# Stm32.net
KiCad netlist of a schematic drawn in Altium Designer
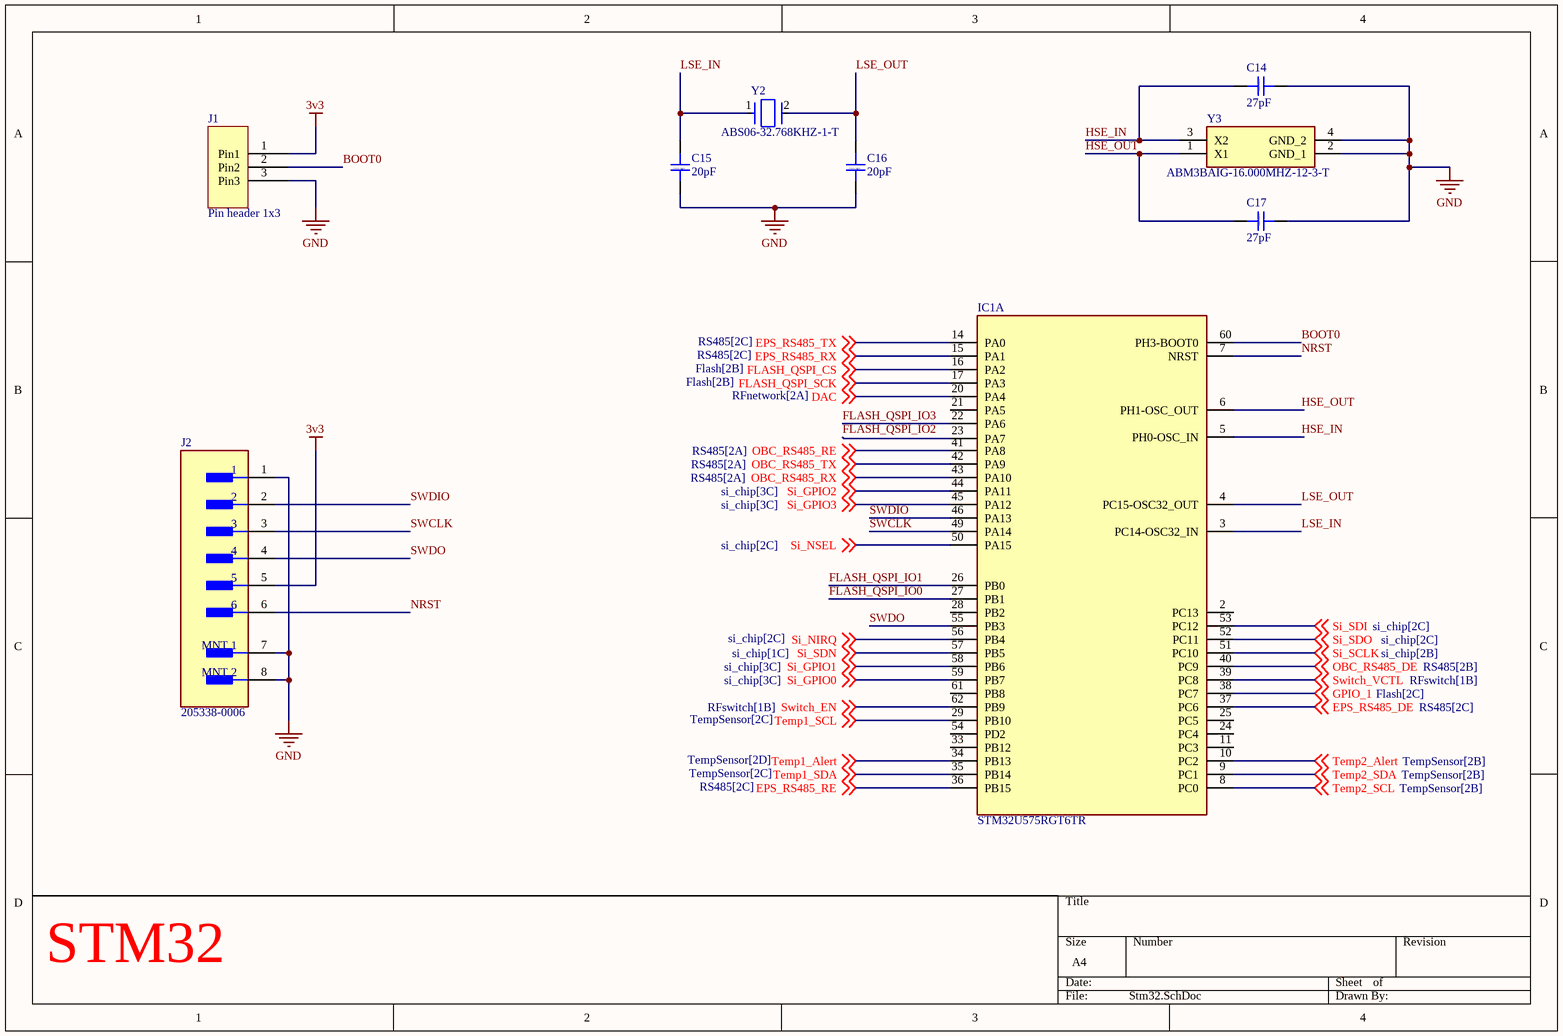
[diagram p0:  Stm32.SchDoc]

(export (version "E")
  (design (tool "Eeschema 10.0.6"))
  (components
    (comp (ref "C14")
      (value "27pF")
      (footprint "CAP_0603")
      (description "Capacitor SMD 0603 RATED")
      (libsource (lib "STeRG-Passives-Standard") (part "Capacitor-SMD-0603"))
    )
    (comp (ref "C15")
      (value "20pF")
      (footprint "CAP_0603")
      (description "Capacitor SMD 0603 RATED")
      (libsource (lib "STeRG-Passives-Standard") (part "Capacitor-SMD-0603"))
    )
    (comp (ref "C16")
      (value "20pF")
      (footprint "CAP_0603")
      (description "Capacitor SMD 0603 RATED")
      (libsource (lib "STeRG-Passives-Standard") (part "Capacitor-SMD-0603"))
    )
    (comp (ref "C17")
      (value "27pF")
      (footprint "CAP_0603")
      (description "Capacitor SMD 0603 RATED")
      (libsource (lib "STeRG-Passives-Standard") (part "Capacitor-SMD-0603"))
    )
    (comp (ref "IC1")
      (value "STM32U575RGT6TR")
      (footprint "QFP50P1200X1200X160-64N")
      (description "Integrated Circuit")
      (fields (field (name "MOUSER PART NUMBER") "511-STM32U575RGT6TR"))
      (libsource (lib "STeRG-ICs-Standard") (part "STM32U575RGT6TR"))
    )
    (comp (ref "J1")
      (value "Pin header 1x3")
      (footprint "HEADER 3")
      (libsource (lib "SamacSys") (part "Pin header 1x3"))
    )
    (comp (ref "J2")
      (value "205338-0006")
      (footprint "FP-2053380006-MFG")
      (libsource (lib "Altium Content Vault") (part "ed24c53d9ba001d1a2a686240a95171"))
    )
    (comp (ref "Y2")
      (value "ABS06-32.768KHZ-1-T")
      (footprint "FP-ABS06-MFG")
      (description "CRYSTAL 32.7680KHZ 12.5PF SMD")
      (fields (field (name "TOLERANCE") "10ppm"))
      (libsource (lib "Altium Content Vault") (part "c23a69dc6c9e2f18f2079038eb95dd1"))
    )
    (comp (ref "Y3")
      (value "ABM3BAIG-16.000MHZ-12-3-T")
      (footprint "SamacSys:ABM3BAIG")
      (description "Crystal or Oscillator")
      (libsource (lib "SamacSys") (part "ABM3BAIG-16.000MHZ-12-3-T"))
    )
  )
  (nets
    (net (code "1") (name "/BOOT0") (class "Default")
      (node (ref "IC1") (pin "60") (pinfunction "PH3-BOOT0_60") (pintype "passive"))
      (node (ref "J1") (pin "2") (pinfunction "Pin2_2") (pintype "passive"))
    )
    (net (code "2") (name "/FLASH_QSPI_IO0") (class "Default")
      (node (ref "IC1") (pin "27") (pinfunction "PB1_27") (pintype "passive"))
    )
    (net (code "3") (name "/FLASH_QSPI_IO1") (class "Default")
      (node (ref "IC1") (pin "26") (pinfunction "PB0_26") (pintype "passive"))
    )
    (net (code "4") (name "/FLASH_QSPI_IO2") (class "Default")
      (node (ref "IC1") (pin "23") (pinfunction "PA7_23") (pintype "passive"))
    )
    (net (code "5") (name "/FLASH_QSPI_IO3") (class "Default")
      (node (ref "IC1") (pin "22") (pinfunction "PA6_22") (pintype "passive"))
    )
    (net (code "6") (name "/HSE_IN") (class "Default")
      (node (ref "C14") (pin "1") (pinfunction "1_1") (pintype "passive"))
      (node (ref "IC1") (pin "5") (pinfunction "PH0-OSC_IN_5") (pintype "passive"))
      (node (ref "Y3") (pin "3") (pinfunction "X2_3") (pintype "passive"))
    )
    (net (code "7") (name "/HSE_OUT") (class "Default")
      (node (ref "C17") (pin "1") (pinfunction "1_1") (pintype "passive"))
      (node (ref "IC1") (pin "6") (pinfunction "PH1-OSC_OUT_6") (pintype "passive"))
      (node (ref "Y3") (pin "1") (pinfunction "X1_1") (pintype "passive"))
    )
    (net (code "8") (name "/LSE_IN") (class "Default")
      (node (ref "C15") (pin "2") (pinfunction "2_2") (pintype "passive"))
      (node (ref "IC1") (pin "3") (pinfunction "PC14-OSC32_IN_3") (pintype "passive"))
      (node (ref "Y2") (pin "1") (pinfunction "1_1") (pintype "passive"))
    )
    (net (code "9") (name "/LSE_OUT") (class "Default")
      (node (ref "C16") (pin "2") (pinfunction "2_2") (pintype "passive"))
      (node (ref "IC1") (pin "4") (pinfunction "PC15-OSC32_OUT_4") (pintype "passive"))
      (node (ref "Y2") (pin "2") (pinfunction "2_2") (pintype "passive"))
    )
    (net (code "10") (name "/NRST") (class "Default")
      (node (ref "IC1") (pin "7") (pinfunction "NRST_7") (pintype "passive"))
      (node (ref "J2") (pin "6") (pinfunction "6_6") (pintype "passive"))
    )
    (net (code "11") (name "/SWCLK") (class "Default")
      (node (ref "IC1") (pin "49") (pinfunction "PA14_49") (pintype "passive"))
      (node (ref "J2") (pin "3") (pinfunction "3_3") (pintype "passive"))
    )
    (net (code "12") (name "/SWDIO") (class "Default")
      (node (ref "IC1") (pin "46") (pinfunction "PA13_46") (pintype "passive"))
      (node (ref "J2") (pin "2") (pinfunction "2_2") (pintype "passive"))
    )
    (net (code "13") (name "/SWDO") (class "Default")
      (node (ref "IC1") (pin "55") (pinfunction "PB3_55") (pintype "passive"))
      (node (ref "J2") (pin "4") (pinfunction "4_4") (pintype "passive"))
    )
    (net (code "14") (name "3v3") (class "Default")
      (node (ref "J1") (pin "1") (pinfunction "Pin1_1") (pintype "passive"))
      (node (ref "J2") (pin "5") (pinfunction "5_5") (pintype "passive"))
    )
    (net (code "15") (name "DAC") (class "Default")
      (node (ref "IC1") (pin "20") (pinfunction "PA4_20") (pintype "passive"))
    )
    (net (code "16") (name "EPS_RS485_DE") (class "Default")
      (node (ref "IC1") (pin "37") (pinfunction "PC6_37") (pintype "passive"))
    )
    (net (code "17") (name "EPS_RS485_RE") (class "Default")
      (node (ref "IC1") (pin "36") (pinfunction "PB15_36") (pintype "passive"))
    )
    (net (code "18") (name "EPS_RS485_RX") (class "Default")
      (node (ref "IC1") (pin "15") (pinfunction "PA1_15") (pintype "passive"))
    )
    (net (code "19") (name "EPS_RS485_TX") (class "Default")
      (node (ref "IC1") (pin "14") (pinfunction "PA0_14") (pintype "passive"))
    )
    (net (code "20") (name "FLASH_QSPI_CS") (class "Default")
      (node (ref "IC1") (pin "16") (pinfunction "PA2_16") (pintype "passive"))
    )
    (net (code "21") (name "FLASH_QSPI_SCK") (class "Default")
      (node (ref "IC1") (pin "17") (pinfunction "PA3_17") (pintype "passive"))
    )
    (net (code "22") (name "GND") (class "Default")
      (node (ref "C14") (pin "2") (pinfunction "2_2") (pintype "passive"))
      (node (ref "C15") (pin "1") (pinfunction "1_1") (pintype "passive"))
      (node (ref "C16") (pin "1") (pinfunction "1_1") (pintype "passive"))
      (node (ref "C17") (pin "2") (pinfunction "2_2") (pintype "passive"))
      (node (ref "J1") (pin "3") (pinfunction "Pin3_3") (pintype "passive"))
      (node (ref "J2") (pin "1") (pinfunction "1_1") (pintype "passive"))
      (node (ref "J2") (pin "7") (pinfunction "MNT_1_7") (pintype "passive"))
      (node (ref "J2") (pin "8") (pinfunction "MNT_2_8") (pintype "passive"))
      (node (ref "Y3") (pin "2") (pinfunction "GND_1_2") (pintype "passive"))
      (node (ref "Y3") (pin "4") (pinfunction "GND_2_4") (pintype "passive"))
    )
    (net (code "23") (name "GPIO_1") (class "Default")
      (node (ref "IC1") (pin "38") (pinfunction "PC7_38") (pintype "passive"))
    )
    (net (code "24") (name "OBC_RS485_DE") (class "Default")
      (node (ref "IC1") (pin "40") (pinfunction "PC9_40") (pintype "passive"))
    )
    (net (code "25") (name "OBC_RS485_RE") (class "Default")
      (node (ref "IC1") (pin "41") (pinfunction "PA8_41") (pintype "passive"))
    )
    (net (code "26") (name "OBC_RS485_RX") (class "Default")
      (node (ref "IC1") (pin "43") (pinfunction "PA10_43") (pintype "passive"))
    )
    (net (code "27") (name "OBC_RS485_TX") (class "Default")
      (node (ref "IC1") (pin "42") (pinfunction "PA9_42") (pintype "passive"))
    )
    (net (code "28") (name "Si_GPIO0") (class "Default")
      (node (ref "IC1") (pin "59") (pinfunction "PB7_59") (pintype "passive"))
    )
    (net (code "29") (name "Si_GPIO1") (class "Default")
      (node (ref "IC1") (pin "58") (pinfunction "PB6_58") (pintype "passive"))
    )
    (net (code "30") (name "Si_GPIO2") (class "Default")
      (node (ref "IC1") (pin "44") (pinfunction "PA11_44") (pintype "passive"))
    )
    (net (code "31") (name "Si_GPIO3") (class "Default")
      (node (ref "IC1") (pin "45") (pinfunction "PA12_45") (pintype "passive"))
    )
    (net (code "32") (name "Si_NIRQ") (class "Default")
      (node (ref "IC1") (pin "56") (pinfunction "PB4_56") (pintype "passive"))
    )
    (net (code "33") (name "Si_NSEL") (class "Default")
      (node (ref "IC1") (pin "50") (pinfunction "PA15_50") (pintype "passive"))
    )
    (net (code "34") (name "Si_SCLK") (class "Default")
      (node (ref "IC1") (pin "51") (pinfunction "PC10_51") (pintype "passive"))
    )
    (net (code "35") (name "Si_SDI") (class "Default")
      (node (ref "IC1") (pin "53") (pinfunction "PC12_53") (pintype "passive"))
    )
    (net (code "36") (name "Si_SDN") (class "Default")
      (node (ref "IC1") (pin "57") (pinfunction "PB5_57") (pintype "passive"))
    )
    (net (code "37") (name "Si_SDO") (class "Default")
      (node (ref "IC1") (pin "52") (pinfunction "PC11_52") (pintype "passive"))
    )
    (net (code "38") (name "Switch_EN") (class "Default")
      (node (ref "IC1") (pin "62") (pinfunction "PB9_62") (pintype "passive"))
    )
    (net (code "39") (name "Switch_VCTL") (class "Default")
      (node (ref "IC1") (pin "39") (pinfunction "PC8_39") (pintype "passive"))
    )
    (net (code "40") (name "Temp1_Alert") (class "Default")
      (node (ref "IC1") (pin "34") (pinfunction "PB13_34") (pintype "passive"))
    )
    (net (code "41") (name "Temp1_SCL") (class "Default")
      (node (ref "IC1") (pin "29") (pinfunction "PB10_29") (pintype "passive"))
    )
    (net (code "42") (name "Temp1_SDA") (class "Default")
      (node (ref "IC1") (pin "35") (pinfunction "PB14_35") (pintype "passive"))
    )
    (net (code "43") (name "Temp2_Alert") (class "Default")
      (node (ref "IC1") (pin "10") (pinfunction "PC2_10") (pintype "passive"))
    )
    (net (code "44") (name "Temp2_SCL") (class "Default")
      (node (ref "IC1") (pin "8") (pinfunction "PC0_8") (pintype "passive"))
    )
    (net (code "45") (name "Temp2_SDA") (class "Default")
      (node (ref "IC1") (pin "9") (pinfunction "PC1_9") (pintype "passive"))
    )
    (net (code "46") (name "unconnected-(IC1A-PA5-Pad21)") (class "Default")
      (node (ref "IC1") (pin "21") (pinfunction "PA5_21") (pintype "passive"))
    )
    (net (code "47") (name "unconnected-(IC1A-PB2-Pad28)") (class "Default")
      (node (ref "IC1") (pin "28") (pinfunction "PB2_28") (pintype "passive"))
    )
    (net (code "48") (name "unconnected-(IC1A-PB8-Pad61)") (class "Default")
      (node (ref "IC1") (pin "61") (pinfunction "PB8_61") (pintype "passive"))
    )
    (net (code "49") (name "unconnected-(IC1A-PB12-Pad33)") (class "Default")
      (node (ref "IC1") (pin "33") (pinfunction "PB12_33") (pintype "passive"))
    )
    (net (code "50") (name "unconnected-(IC1A-PC3-Pad11)") (class "Default")
      (node (ref "IC1") (pin "11") (pinfunction "PC3_11") (pintype "passive"))
    )
    (net (code "51") (name "unconnected-(IC1A-PC4-Pad24)") (class "Default")
      (node (ref "IC1") (pin "24") (pinfunction "PC4_24") (pintype "passive"))
    )
    (net (code "52") (name "unconnected-(IC1A-PC5-Pad25)") (class "Default")
      (node (ref "IC1") (pin "25") (pinfunction "PC5_25") (pintype "passive"))
    )
    (net (code "53") (name "unconnected-(IC1A-PC13-Pad2)") (class "Default")
      (node (ref "IC1") (pin "2") (pinfunction "PC13_2") (pintype "passive"))
    )
    (net (code "54") (name "unconnected-(IC1A-PD2-Pad54)") (class "Default")
      (node (ref "IC1") (pin "54") (pinfunction "PD2_54") (pintype "passive"))
    )
  )
)
